# 4_cpu.net
KiCad netlist of a schematic drawn in Altium Designer
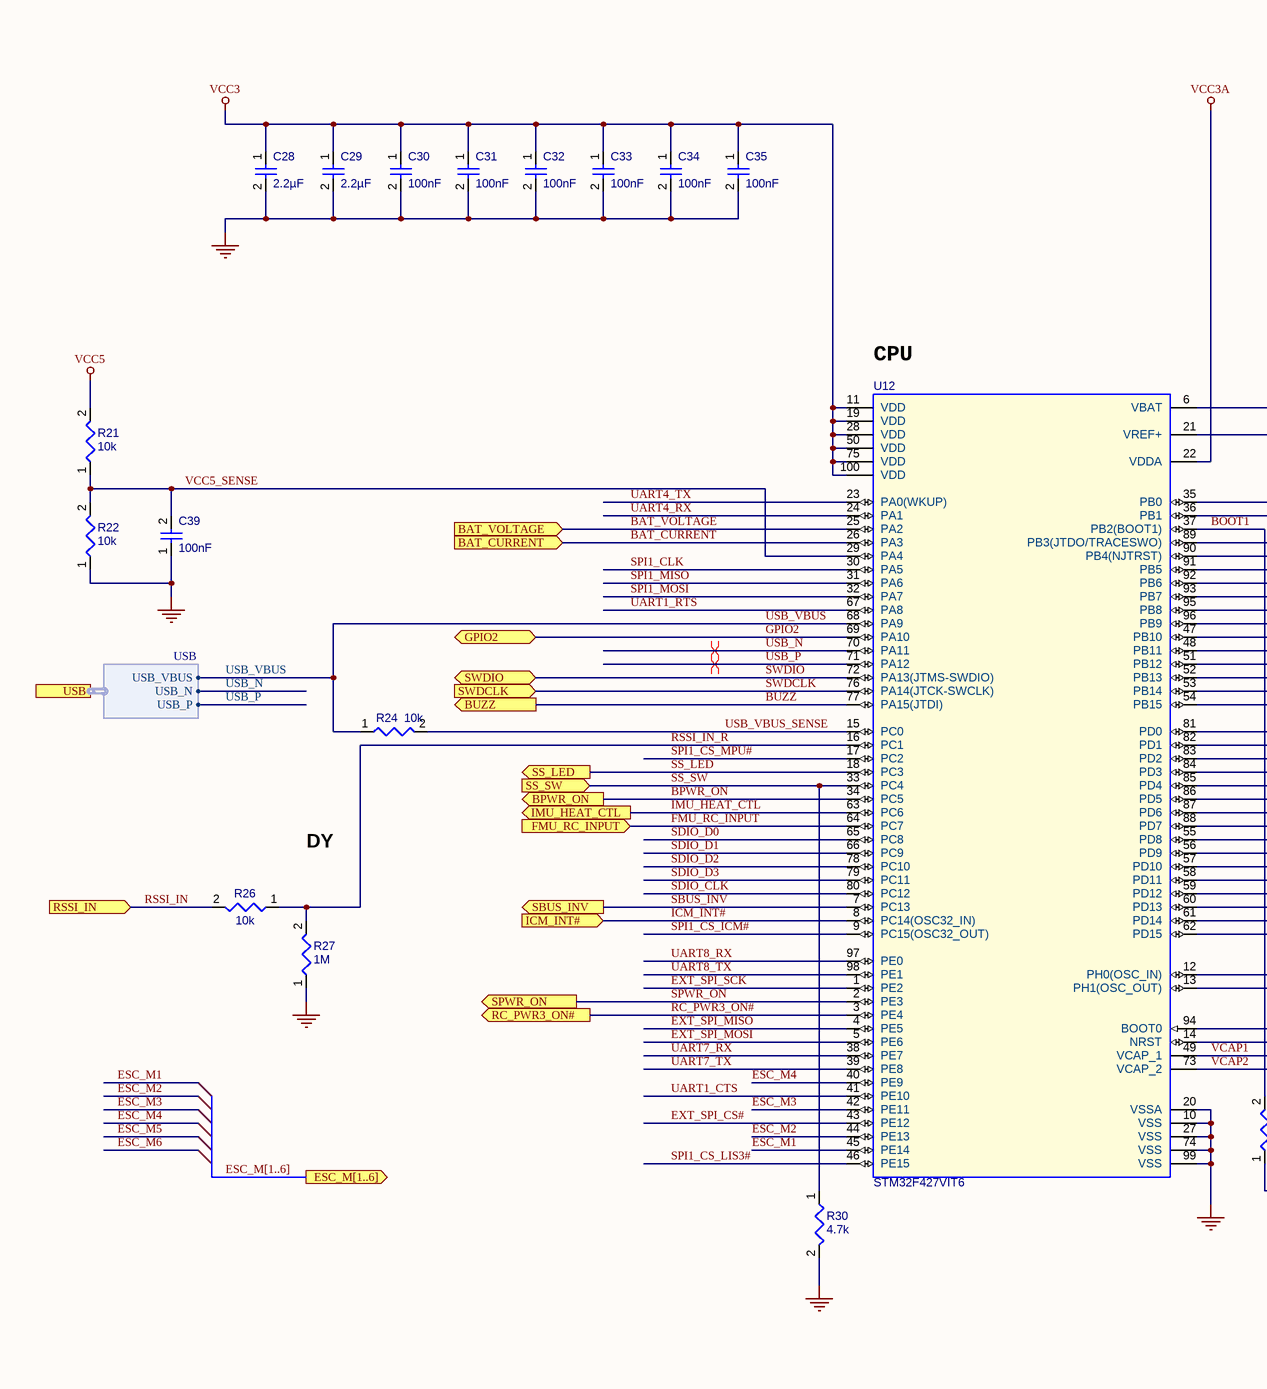
[diagram p0: 4_cpu.SchDoc, left]
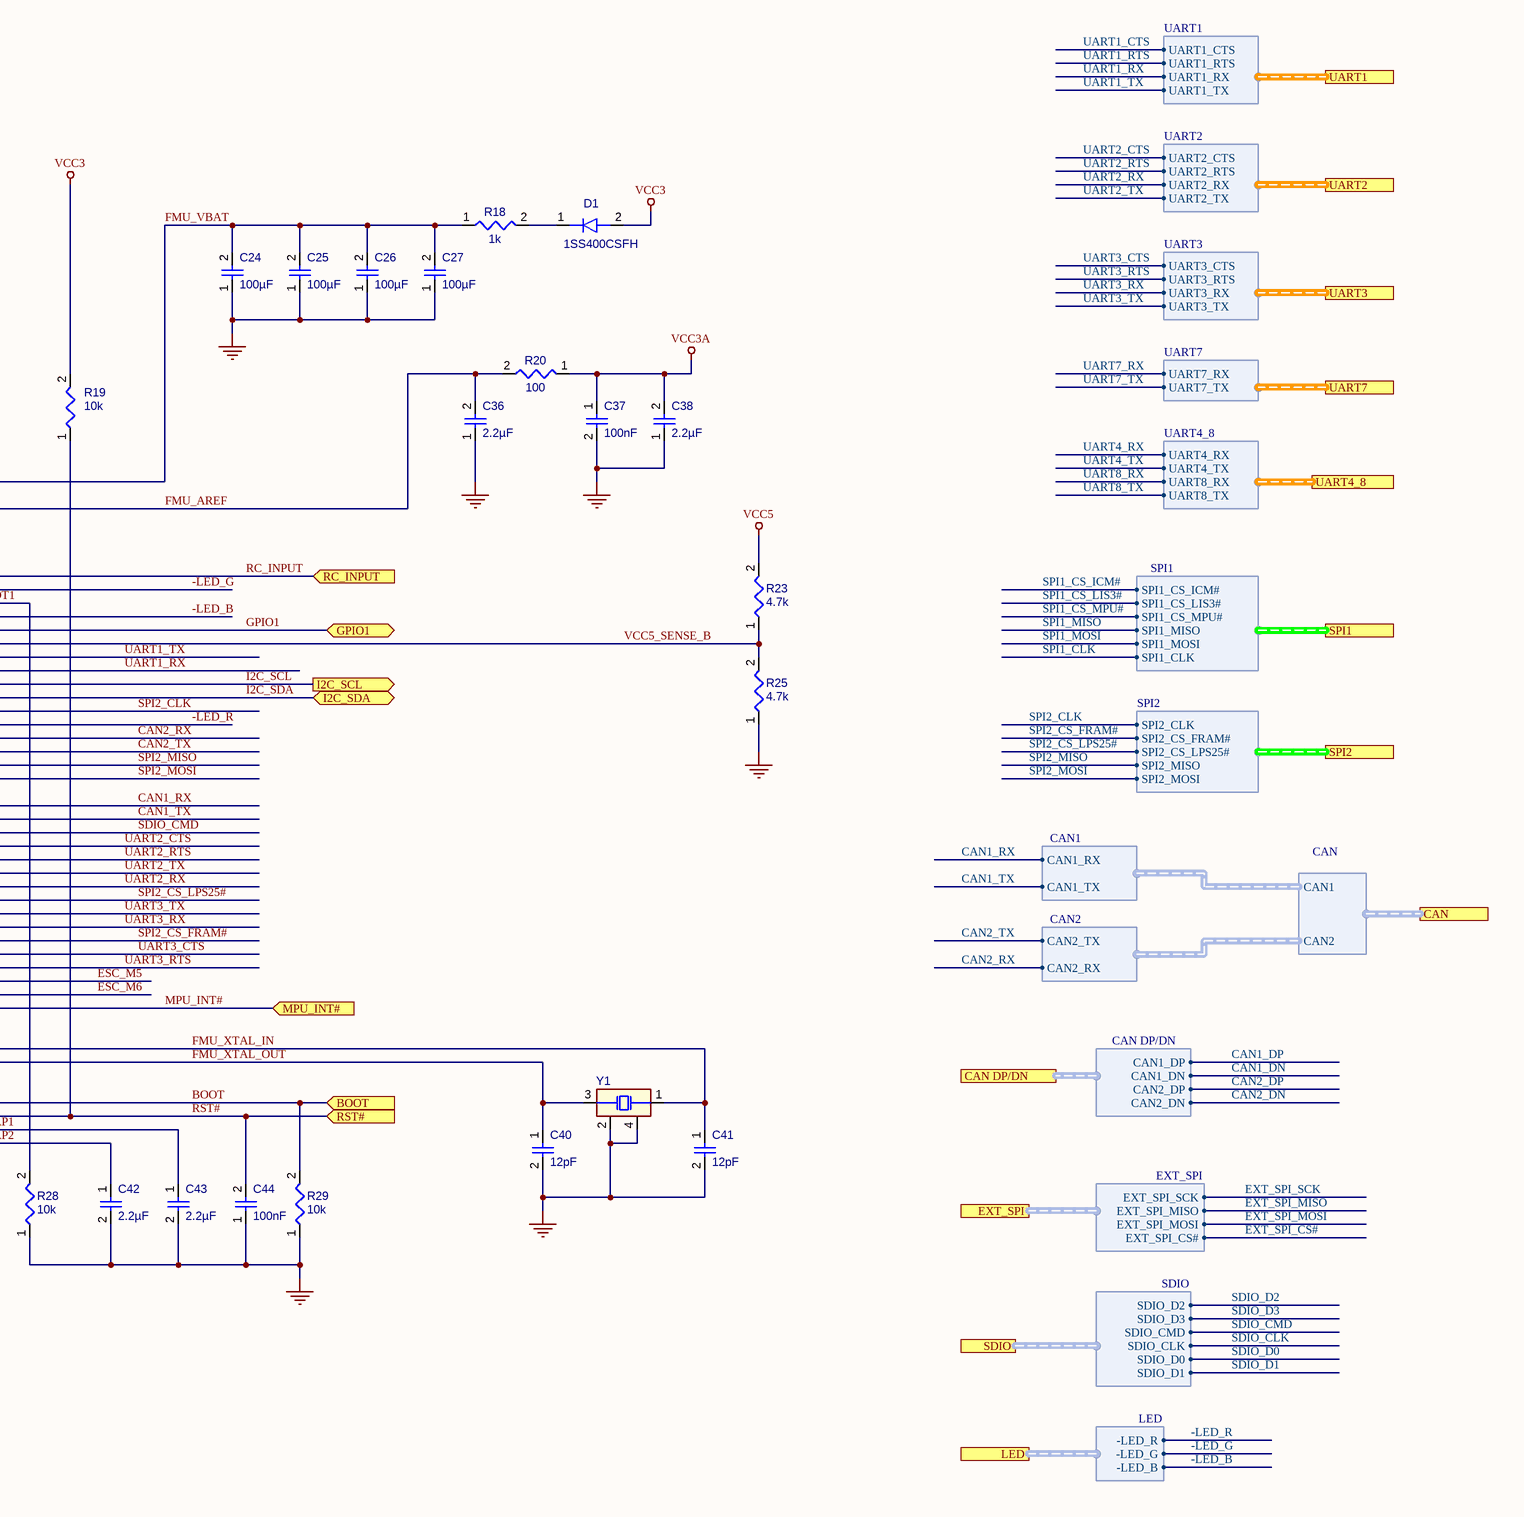
[diagram p1: 4_cpu.SchDoc, right]

(export (version "E")
  (design (tool "Eeschema 10.0.6"))
  (components
    (comp (ref "C24")
      (value "100µF")
      (footprint "CAPC0805(2012)145_L")
      (description "Chip Capacitor, 100µF +/-20%, 6.3V, 0805, Thickness 1.45 mm")
      (fields (field (name "TOLERANCE") "10%") (field (name "Comment") "Capacitor 100µF +/-20% 6.3V 0805"))
      (libsource (lib "<Company> Server") (part "CAP-NP-2"))
    )
    (comp (ref "C25")
      (value "100µF")
      (footprint "CAPC0805(2012)145_L")
      (description "Chip Capacitor, 100µF +/-20%, 6.3V, 0805, Thickness 1.45 mm")
      (fields (field (name "TOLERANCE") "10%") (field (name "Comment") "Capacitor 100µF +/-20% 6.3V 0805"))
      (libsource (lib "<Company> Server") (part "CAP-NP-2"))
    )
    (comp (ref "C26")
      (value "100µF")
      (footprint "CAPC0805(2012)145_L")
      (description "Chip Capacitor, 100µF +/-20%, 6.3V, 0805, Thickness 1.45 mm")
      (fields (field (name "TOLERANCE") "10%") (field (name "Comment") "Capacitor 100µF +/-20% 6.3V 0805"))
      (libsource (lib "<Company> Server") (part "CAP-NP-2"))
    )
    (comp (ref "C27")
      (value "100µF")
      (footprint "CAPC0805(2012)145_L")
      (description "Chip Capacitor, 100µF +/-20%, 6.3V, 0805, Thickness 1.45 mm")
      (fields (field (name "TOLERANCE") "10%") (field (name "Comment") "Capacitor 100µF +/-20% 6.3V 0805"))
      (libsource (lib "<Company> Server") (part "CAP-NP-2"))
    )
    (comp (ref "C28")
      (value "2.2µF")
      (footprint "CAPC0402(1005)60_L")
      (description "Chip Capacitor, 2,2µF +/-20%, 10V, 0402, Thickness 0.6 mm")
      (fields (field (name "TOLERANCE") "10%") (field (name "Comment") "Capacitor 2,2µF +/-20% 10V 0402"))
      (libsource (lib "<Company> Server") (part "CAP-NP-2"))
    )
    (comp (ref "C29")
      (value "2.2µF")
      (footprint "CAPC0402(1005)60_L")
      (description "Chip Capacitor, 2,2µF +/-20%, 10V, 0402, Thickness 0.6 mm")
      (fields (field (name "TOLERANCE") "10%") (field (name "Comment") "Capacitor 2,2µF +/-20% 10V 0402"))
      (libsource (lib "<Company> Server") (part "CAP-NP-2"))
    )
    (comp (ref "C30")
      (value "100nF")
      (footprint "CAPC0402(1005)60_L")
      (description "Chip Capacitor, 100nF +/-20%, 10V, 0402, Thickness 0.6 mm")
      (fields (field (name "TOLERANCE") "20%") (field (name "Comment") "Capacitor 100nF +/-20% 10V 0402"))
      (libsource (lib "<Company> Server") (part "CAP-NP-2"))
    )
    (comp (ref "C31")
      (value "100nF")
      (footprint "CAPC0402(1005)60_L")
      (description "Chip Capacitor, 100nF +/-20%, 10V, 0402, Thickness 0.6 mm")
      (fields (field (name "TOLERANCE") "20%") (field (name "Comment") "Capacitor 100nF +/-20% 10V 0402"))
      (libsource (lib "<Company> Server") (part "CAP-NP-2"))
    )
    (comp (ref "C32")
      (value "100nF")
      (footprint "CAPC0402(1005)60_L")
      (description "Chip Capacitor, 100nF +/-20%, 10V, 0402, Thickness 0.6 mm")
      (fields (field (name "TOLERANCE") "20%") (field (name "Comment") "Capacitor 100nF +/-20% 10V 0402"))
      (libsource (lib "<Company> Server") (part "CAP-NP-2"))
    )
    (comp (ref "C33")
      (value "100nF")
      (footprint "CAPC0402(1005)60_L")
      (description "Chip Capacitor, 100nF +/-20%, 10V, 0402, Thickness 0.6 mm")
      (fields (field (name "TOLERANCE") "20%") (field (name "Comment") "Capacitor 100nF +/-20% 10V 0402"))
      (libsource (lib "<Company> Server") (part "CAP-NP-2"))
    )
    (comp (ref "C34")
      (value "100nF")
      (footprint "CAPC0402(1005)60_L")
      (description "Chip Capacitor, 100nF +/-20%, 10V, 0402, Thickness 0.6 mm")
      (fields (field (name "TOLERANCE") "20%") (field (name "Comment") "Capacitor 100nF +/-20% 10V 0402"))
      (libsource (lib "<Company> Server") (part "CAP-NP-2"))
    )
    (comp (ref "C35")
      (value "100nF")
      (footprint "CAPC0402(1005)60_L")
      (description "Chip Capacitor, 100nF +/-20%, 10V, 0402, Thickness 0.6 mm")
      (fields (field (name "TOLERANCE") "20%") (field (name "Comment") "Capacitor 100nF +/-20% 10V 0402"))
      (libsource (lib "<Company> Server") (part "CAP-NP-2"))
    )
    (comp (ref "C36")
      (value "2.2µF")
      (footprint "CAPC0402(1005)60_L")
      (description "Chip Capacitor, 2,2µF +/-20%, 10V, 0402, Thickness 0.6 mm")
      (fields (field (name "TOLERANCE") "10%") (field (name "Comment") "Capacitor 2,2µF +/-20% 10V 0402"))
      (libsource (lib "<Company> Server") (part "CAP-NP-2"))
    )
    (comp (ref "C37")
      (value "100nF")
      (footprint "CAPC0402(1005)60_L")
      (description "Chip Capacitor, 100nF +/-20%, 10V, 0402, Thickness 0.6 mm")
      (fields (field (name "TOLERANCE") "20%") (field (name "Comment") "Capacitor 100nF +/-20% 10V 0402"))
      (libsource (lib "<Company> Server") (part "CAP-NP-2"))
    )
    (comp (ref "C38")
      (value "2.2µF")
      (footprint "CAPC0402(1005)60_L")
      (description "Chip Capacitor, 2,2µF +/-20%, 10V, 0402, Thickness 0.6 mm")
      (fields (field (name "TOLERANCE") "10%") (field (name "Comment") "Capacitor 2,2µF +/-20% 10V 0402"))
      (libsource (lib "<Company> Server") (part "CAP-NP-2"))
    )
    (comp (ref "C39")
      (value "100nF")
      (footprint "CAPC0402(1005)60_L")
      (description "Chip Capacitor, 100nF +/-20%, 10V, 0402, Thickness 0.6 mm")
      (fields (field (name "TOLERANCE") "20%") (field (name "Comment") "Capacitor 100nF +/-20% 10V 0402"))
      (libsource (lib "<Company> Server") (part "CAP-NP-2"))
    )
    (comp (ref "C40")
      (value "12pF")
      (footprint "CAPC0402(1005)33_L")
      (description "Chip Capacitor, 12pF +/-10%, 50V, 0402, Thickness 0.33 mm")
      (fields (field (name "TOLERANCE") "20%") (field (name "Comment") "Capacitor 12pF +/-10% 50V 0402"))
      (libsource (lib "<Company> Server") (part "CAP-NP-2"))
    )
    (comp (ref "C41")
      (value "12pF")
      (footprint "CAPC0402(1005)33_L")
      (description "Chip Capacitor, 12pF +/-10%, 50V, 0402, Thickness 0.33 mm")
      (fields (field (name "TOLERANCE") "20%") (field (name "Comment") "Capacitor 12pF +/-10% 50V 0402"))
      (libsource (lib "<Company> Server") (part "CAP-NP-2"))
    )
    (comp (ref "C42")
      (value "2.2µF")
      (footprint "CAPC0402(1005)60_L")
      (description "Chip Capacitor, 2,2µF +/-20%, 10V, 0402, Thickness 0.6 mm")
      (fields (field (name "TOLERANCE") "10%") (field (name "Comment") "Capacitor 2,2µF +/-20% 10V 0402"))
      (libsource (lib "<Company> Server") (part "CAP-NP-2"))
    )
    (comp (ref "C43")
      (value "2.2µF")
      (footprint "CAPC0402(1005)60_L")
      (description "Chip Capacitor, 2,2µF +/-20%, 10V, 0402, Thickness 0.6 mm")
      (fields (field (name "TOLERANCE") "10%") (field (name "Comment") "Capacitor 2,2µF +/-20% 10V 0402"))
      (libsource (lib "<Company> Server") (part "CAP-NP-2"))
    )
    (comp (ref "C44")
      (value "100nF")
      (footprint "CAPC0402(1005)60_L")
      (description "Chip Capacitor, 100nF +/-20%, 10V, 0402, Thickness 0.6 mm")
      (fields (field (name "TOLERANCE") "20%") (field (name "Comment") "Capacitor 100nF +/-20% 10V 0402"))
      (libsource (lib "<Company> Server") (part "CAP-NP-2"))
    )
    (comp (ref "D1")
      (value "1SS400CSFH")
      (footprint "ROHM-VMN2-2_V")
      (description "Switching Diode (High Speed Switching), 80 V, 100 mA, 2-Pin SOD-923, RoHS, Tape and Reel")
      (libsource (lib "<Company> Server") (part "D-KA-2"))
    )
    (comp (ref "R18")
      (value "1k")
      (footprint "RESC0402(1005)_L")
      (description "Chip Resistor, 1 kOhms, +/-5 %, 63 mW, -55 to 155 degC, 0402")
      (fields (field (name "TOLERANCE") "5%") (field (name "POWER") "63mW"))
      (libsource (lib "<Company> Server") (part "RES-2"))
    )
    (comp (ref "R19")
      (value "10k")
      (footprint "RESC0402(1005)_L")
      (description "Chip Resistor, 10 kOhms, +/-1 %, 63 mW, -55 to 125 degC, 0402")
      (fields (field (name "TOLERANCE") "1%") (field (name "POWER") "63mW"))
      (libsource (lib "<Company> Server") (part "RES-2"))
    )
    (comp (ref "R20")
      (value "100")
      (footprint "RESC0402(1005)_L")
      (description "Chip Resistor, 100 Ohms, +/-1 %, 63 mW, -55 to 155 degC, 0402")
      (fields (field (name "TOLERANCE") "1%") (field (name "POWER") "63mW"))
      (libsource (lib "<Company> Server") (part "RES-2"))
    )
    (comp (ref "R21")
      (value "10k")
      (footprint "RESC0402(1005)_L")
      (description "Chip Resistor, 10 kOhms, +/-1 %, 63 mW, -55 to 125 degC, 0402")
      (fields (field (name "TOLERANCE") "1%") (field (name "POWER") "63mW"))
      (libsource (lib "<Company> Server") (part "RES-2"))
    )
    (comp (ref "R22")
      (value "10k")
      (footprint "RESC0402(1005)_L")
      (description "Chip Resistor, 10 kOhms, +/-1 %, 63 mW, -55 to 125 degC, 0402")
      (fields (field (name "TOLERANCE") "1%") (field (name "POWER") "63mW"))
      (libsource (lib "<Company> Server") (part "RES-2"))
    )
    (comp (ref "R23")
      (value "4.7k")
      (footprint "RESC0402(1005)_L")
      (description "Chip Resistor, 4,7 kOhms, +/-1 %, 63 mW, -55 to 155 degC, 0402")
      (fields (field (name "TOLERANCE") "1%") (field (name "POWER") "63mW"))
      (libsource (lib "<Company> Server") (part "RES-2"))
    )
    (comp (ref "R24")
      (value "10k")
      (footprint "RESC0402(1005)_L")
      (description "Chip Resistor, 10 kOhms, +/-1 %, 63 mW, -55 to 125 degC, 0402")
      (fields (field (name "TOLERANCE") "1%") (field (name "POWER") "63mW"))
      (libsource (lib "<Company> Server") (part "RES-2"))
    )
    (comp (ref "R25")
      (value "4.7k")
      (footprint "RESC0402(1005)_L")
      (description "Chip Resistor, 4,7 kOhms, +/-1 %, 63 mW, -55 to 155 degC, 0402")
      (fields (field (name "TOLERANCE") "1%") (field (name "POWER") "63mW"))
      (libsource (lib "<Company> Server") (part "RES-2"))
    )
    (comp (ref "R26")
      (value "10k")
      (footprint "RESC0402(1005)_L")
      (description "Chip Resistor, 10 kOhms, +/-1 %, 63 mW, -55 to 125 degC, 0402")
      (fields (field (name "TOLERANCE") "1%") (field (name "POWER") "63mW"))
      (libsource (lib "<Company> Server") (part "RES-2"))
    )
    (comp (ref "R27")
      (value "1M")
      (footprint "RESC0402(1005)_L")
      (description "Chip Resistor, 1 MOhms, +/-5 %, 63 mW, -55 to 155 degC, 0402")
      (fields (field (name "TOLERANCE") "5%") (field (name "POWER") "63mW"))
      (libsource (lib "<Company> Server") (part "RES-2"))
    )
    (comp (ref "R28")
      (value "10k")
      (footprint "RESC0402(1005)_L")
      (description "Chip Resistor, 10 kOhms, +/-1 %, 63 mW, -55 to 125 degC, 0402")
      (fields (field (name "TOLERANCE") "1%") (field (name "POWER") "63mW"))
      (libsource (lib "<Company> Server") (part "RES-2"))
    )
    (comp (ref "R29")
      (value "10k")
      (footprint "RESC0402(1005)_L")
      (description "Chip Resistor, 10 kOhms, +/-1 %, 63 mW, -55 to 125 degC, 0402")
      (fields (field (name "TOLERANCE") "1%") (field (name "POWER") "63mW"))
      (libsource (lib "<Company> Server") (part "RES-2"))
    )
    (comp (ref "R30")
      (value "4.7k")
      (footprint "RESC0402(1005)_L")
      (description "Chip Resistor, 4,7 kOhms, +/-1 %, 63 mW, -55 to 155 degC, 0402")
      (fields (field (name "TOLERANCE") "1%") (field (name "POWER") "63mW"))
      (libsource (lib "<Company> Server") (part "RES-2"))
    )
    (comp (ref "U12")
      (value "STM32F427VIT6")
      (footprint "STM-LQFP100")
      (libsource (lib "<Company> Server") (part "CMP-00125-5"))
    )
    (comp (ref "Y1")
      (value "FA-12824.0000MF10Z-W3")
      (footprint "EPSON-FA-128_V")
      (description "Crystal, 24 MHz, +/- 10 ppm, -20 to 75 degC, 4-Pin SMD, RoHS, Tape and Reel")
      (libsource (lib "<Company> Server") (part "CMP-00014-7"))
    )
  )
  (nets
    (net (code "16") (name "/-LED_B") (class "Default")
      (node (ref "U12") (pin "89") (pinfunction "PB3(JTDO/TRACESWO)_89") (pintype "bidirectional"))
    )
    (net (code "17") (name "/-LED_G") (class "Default")
      (node (ref "U12") (pin "36") (pinfunction "PB1_36") (pintype "bidirectional"))
    )
    (net (code "18") (name "/-LED_R") (class "Default")
      (node (ref "U12") (pin "48") (pinfunction "PB11_48") (pintype "bidirectional"))
    )
    (net (code "19") (name "/BAT_CURRENT") (class "Default")
      (node (ref "U12") (pin "26") (pinfunction "PA3_26") (pintype "bidirectional"))
    )
    (net (code "20") (name "/BAT_VOLTAGE") (class "Default")
      (node (ref "U12") (pin "25") (pinfunction "PA2_25") (pintype "bidirectional"))
    )
    (net (code "21") (name "/BOOT") (class "Default")
      (node (ref "R29") (pin "2") (pinfunction "2_2") (pintype "passive"))
      (node (ref "U12") (pin "94") (pinfunction "BOOT0_94") (pintype "input"))
    )
    (net (code "22") (name "/BOOT1") (class "Default")
      (node (ref "R28") (pin "2") (pinfunction "2_2") (pintype "passive"))
      (node (ref "U12") (pin "37") (pinfunction "PB2(BOOT1)_37") (pintype "bidirectional"))
    )
    (net (code "23") (name "/BPWR_ON") (class "Default")
      (node (ref "U12") (pin "34") (pinfunction "PC5_34") (pintype "bidirectional"))
    )
    (net (code "24") (name "/BUZZ") (class "Default")
      (node (ref "U12") (pin "77") (pinfunction "PA15(JTDI)_77") (pintype "bidirectional"))
    )
    (net (code "27") (name "/CAN1_RX") (class "Default")
      (node (ref "U12") (pin "81") (pinfunction "PD0_81") (pintype "bidirectional"))
    )
    (net (code "28") (name "/CAN1_TX") (class "Default")
      (node (ref "U12") (pin "82") (pinfunction "PD1_82") (pintype "bidirectional"))
    )
    (net (code "31") (name "/CAN2_RX") (class "Default")
      (node (ref "U12") (pin "51") (pinfunction "PB12_51") (pintype "bidirectional"))
    )
    (net (code "32") (name "/CAN2_TX") (class "Default")
      (node (ref "U12") (pin "52") (pinfunction "PB13_52") (pintype "bidirectional"))
    )
    (net (code "34") (name "/ESC_M1") (class "Default")
      (node (ref "U12") (pin "45") (pinfunction "PE14_45") (pintype "bidirectional"))
    )
    (net (code "35") (name "/ESC_M2") (class "Default")
      (node (ref "U12") (pin "44") (pinfunction "PE13_44") (pintype "bidirectional"))
    )
    (net (code "36") (name "/ESC_M3") (class "Default")
      (node (ref "U12") (pin "42") (pinfunction "PE11_42") (pintype "bidirectional"))
    )
    (net (code "37") (name "/ESC_M4") (class "Default")
      (node (ref "U12") (pin "40") (pinfunction "PE9_40") (pintype "bidirectional"))
    )
    (net (code "38") (name "/ESC_M5") (class "Default")
      (node (ref "U12") (pin "60") (pinfunction "PD13_60") (pintype "bidirectional"))
    )
    (net (code "39") (name "/ESC_M6") (class "Default")
      (node (ref "U12") (pin "61") (pinfunction "PD14_61") (pintype "bidirectional"))
    )
    (net (code "41") (name "/EXT_SPI_CS#") (class "Default")
      (node (ref "U12") (pin "43") (pinfunction "PE12_43") (pintype "bidirectional"))
    )
    (net (code "42") (name "/EXT_SPI_MISO") (class "Default")
      (node (ref "U12") (pin "4") (pinfunction "PE5_4") (pintype "bidirectional"))
    )
    (net (code "43") (name "/EXT_SPI_MOSI") (class "Default")
      (node (ref "U12") (pin "5") (pinfunction "PE6_5") (pintype "bidirectional"))
    )
    (net (code "44") (name "/EXT_SPI_SCK") (class "Default")
      (node (ref "U12") (pin "1") (pinfunction "PE2_1") (pintype "bidirectional"))
    )
    (net (code "45") (name "/FMU_AREF") (class "Default")
      (node (ref "C36") (pin "2") (pinfunction "2_2") (pintype "passive"))
      (node (ref "R20") (pin "2") (pinfunction "2_2") (pintype "passive"))
      (node (ref "U12") (pin "21") (pinfunction "VREF+_21") (pintype "power_in"))
    )
    (net (code "46") (name "/FMU_RC_INPUT") (class "Default")
      (node (ref "U12") (pin "64") (pinfunction "PC7_64") (pintype "bidirectional"))
    )
    (net (code "47") (name "/FMU_VBAT") (class "Default")
      (node (ref "C24") (pin "2") (pinfunction "2_2") (pintype "passive"))
      (node (ref "C25") (pin "2") (pinfunction "2_2") (pintype "passive"))
      (node (ref "C26") (pin "2") (pinfunction "2_2") (pintype "passive"))
      (node (ref "C27") (pin "2") (pinfunction "2_2") (pintype "passive"))
      (node (ref "R18") (pin "1") (pinfunction "1_1") (pintype "passive"))
      (node (ref "U12") (pin "6") (pinfunction "VBAT_6") (pintype "power_in"))
    )
    (net (code "48") (name "/FMU_XTAL_IN") (class "Default")
      (node (ref "C41") (pin "1") (pinfunction "1_1") (pintype "passive"))
      (node (ref "U12") (pin "12") (pinfunction "PH0(OSC_IN)_12") (pintype "bidirectional"))
      (node (ref "Y1") (pin "1") (pinfunction "X1_1") (pintype "passive"))
    )
    (net (code "49") (name "/FMU_XTAL_OUT") (class "Default")
      (node (ref "C40") (pin "1") (pinfunction "1_1") (pintype "passive"))
      (node (ref "U12") (pin "13") (pinfunction "PH1(OSC_OUT)_13") (pintype "bidirectional"))
      (node (ref "Y1") (pin "3") (pinfunction "X2_3") (pintype "passive"))
    )
    (net (code "50") (name "/GPIO1") (class "Default")
      (node (ref "U12") (pin "90") (pinfunction "PB4(NJTRST)_90") (pintype "bidirectional"))
    )
    (net (code "51") (name "/GPIO2") (class "Default")
      (node (ref "U12") (pin "69") (pinfunction "PA10_69") (pintype "bidirectional"))
    )
    (net (code "52") (name "/I2C_SCL") (class "Default")
      (node (ref "U12") (pin "95") (pinfunction "PB8_95") (pintype "bidirectional"))
    )
    (net (code "53") (name "/I2C_SDA") (class "Default")
      (node (ref "U12") (pin "96") (pinfunction "PB9_96") (pintype "bidirectional"))
    )
    (net (code "54") (name "/ICM_INT#") (class "Default")
      (node (ref "U12") (pin "8") (pinfunction "PC14(OSC32_IN)_8") (pintype "bidirectional"))
    )
    (net (code "55") (name "/IMU_HEAT_CTL") (class "Default")
      (node (ref "U12") (pin "63") (pinfunction "PC6_63") (pintype "bidirectional"))
    )
    (net (code "56") (name "/MPU_INT#") (class "Default")
      (node (ref "U12") (pin "62") (pinfunction "PD15_62") (pintype "bidirectional"))
    )
    (net (code "57") (name "/RC_INPUT") (class "Default")
      (node (ref "U12") (pin "35") (pinfunction "PB0_35") (pintype "bidirectional"))
    )
    (net (code "58") (name "/RC_PWR3_ON#") (class "Default")
      (node (ref "U12") (pin "3") (pinfunction "PE4_3") (pintype "bidirectional"))
    )
    (net (code "59") (name "/RSSI_IN") (class "Default")
      (node (ref "R26") (pin "2") (pinfunction "2_2") (pintype "passive"))
    )
    (net (code "60") (name "/RSSI_IN_R") (class "Default")
      (node (ref "R26") (pin "1") (pinfunction "1_1") (pintype "passive"))
      (node (ref "R27") (pin "2") (pinfunction "2_2") (pintype "passive"))
      (node (ref "U12") (pin "16") (pinfunction "PC1_16") (pintype "bidirectional"))
    )
    (net (code "61") (name "/RST#") (class "Default")
      (node (ref "C44") (pin "2") (pinfunction "2_2") (pintype "passive"))
      (node (ref "R19") (pin "1") (pinfunction "1_1") (pintype "passive"))
      (node (ref "U12") (pin "14") (pinfunction "NRST_14") (pintype "bidirectional"))
    )
    (net (code "62") (name "/SBUS_INV") (class "Default")
      (node (ref "U12") (pin "7") (pinfunction "PC13_7") (pintype "bidirectional"))
    )
    (net (code "63") (name "/SDIO_CLK") (class "Default")
      (node (ref "U12") (pin "80") (pinfunction "PC12_80") (pintype "bidirectional"))
    )
    (net (code "64") (name "/SDIO_CMD") (class "Default")
      (node (ref "U12") (pin "83") (pinfunction "PD2_83") (pintype "bidirectional"))
    )
    (net (code "65") (name "/SDIO_D0") (class "Default")
      (node (ref "U12") (pin "65") (pinfunction "PC8_65") (pintype "bidirectional"))
    )
    (net (code "66") (name "/SDIO_D1") (class "Default")
      (node (ref "U12") (pin "66") (pinfunction "PC9_66") (pintype "bidirectional"))
    )
    (net (code "67") (name "/SDIO_D2") (class "Default")
      (node (ref "U12") (pin "78") (pinfunction "PC10_78") (pintype "bidirectional"))
    )
    (net (code "68") (name "/SDIO_D3") (class "Default")
      (node (ref "U12") (pin "79") (pinfunction "PC11_79") (pintype "bidirectional"))
    )
    (net (code "69") (name "/SPI1_CLK") (class "Default")
      (node (ref "U12") (pin "30") (pinfunction "PA5_30") (pintype "bidirectional"))
    )
    (net (code "70") (name "/SPI1_CS_ICM#") (class "Default")
      (node (ref "U12") (pin "9") (pinfunction "PC15(OSC32_OUT)_9") (pintype "bidirectional"))
    )
    (net (code "71") (name "/SPI1_CS_LIS3#") (class "Default")
      (node (ref "U12") (pin "46") (pinfunction "PE15_46") (pintype "bidirectional"))
    )
    (net (code "72") (name "/SPI1_CS_MPU#") (class "Default")
      (node (ref "U12") (pin "17") (pinfunction "PC2_17") (pintype "bidirectional"))
    )
    (net (code "73") (name "/SPI1_MISO") (class "Default")
      (node (ref "U12") (pin "31") (pinfunction "PA6_31") (pintype "bidirectional"))
    )
    (net (code "74") (name "/SPI1_MOSI") (class "Default")
      (node (ref "U12") (pin "32") (pinfunction "PA7_32") (pintype "bidirectional"))
    )
    (net (code "75") (name "/SPI2_CLK") (class "Default")
      (node (ref "U12") (pin "47") (pinfunction "PB10_47") (pintype "bidirectional"))
    )
    (net (code "76") (name "/SPI2_CS_FRAM#") (class "Default")
      (node (ref "U12") (pin "57") (pinfunction "PD10_57") (pintype "bidirectional"))
    )
    (net (code "77") (name "/SPI2_CS_LPS25#") (class "Default")
      (node (ref "U12") (pin "88") (pinfunction "PD7_88") (pintype "bidirectional"))
    )
    (net (code "78") (name "/SPI2_MISO") (class "Default")
      (node (ref "U12") (pin "53") (pinfunction "PB14_53") (pintype "bidirectional"))
    )
    (net (code "79") (name "/SPI2_MOSI") (class "Default")
      (node (ref "U12") (pin "54") (pinfunction "PB15_54") (pintype "bidirectional"))
    )
    (net (code "80") (name "/SPWR_ON") (class "Default")
      (node (ref "U12") (pin "2") (pinfunction "PE3_2") (pintype "bidirectional"))
    )
    (net (code "81") (name "/SS_LED") (class "Default")
      (node (ref "U12") (pin "18") (pinfunction "PC3_18") (pintype "bidirectional"))
    )
    (net (code "82") (name "/SS_SW") (class "Default")
      (node (ref "R30") (pin "1") (pinfunction "1_1") (pintype "passive"))
      (node (ref "U12") (pin "33") (pinfunction "PC4_33") (pintype "bidirectional"))
    )
    (net (code "83") (name "/SWDCLK") (class "Default")
      (node (ref "U12") (pin "76") (pinfunction "PA14(JTCK-SWCLK)_76") (pintype "bidirectional"))
    )
    (net (code "84") (name "/SWDIO") (class "Default")
      (node (ref "U12") (pin "72") (pinfunction "PA13(JTMS-SWDIO)_72") (pintype "bidirectional"))
    )
    (net (code "85") (name "/UART1_CTS") (class "Default")
      (node (ref "U12") (pin "41") (pinfunction "PE10_41") (pintype "bidirectional"))
    )
    (net (code "86") (name "/UART1_RTS") (class "Default")
      (node (ref "U12") (pin "67") (pinfunction "PA8_67") (pintype "bidirectional"))
    )
    (net (code "87") (name "/UART1_RX") (class "Default")
      (node (ref "U12") (pin "93") (pinfunction "PB7_93") (pintype "bidirectional"))
    )
    (net (code "88") (name "/UART1_TX") (class "Default")
      (node (ref "U12") (pin "92") (pinfunction "PB6_92") (pintype "bidirectional"))
    )
    (net (code "89") (name "/UART2_CTS") (class "Default")
      (node (ref "U12") (pin "84") (pinfunction "PD3_84") (pintype "bidirectional"))
    )
    (net (code "90") (name "/UART2_RTS") (class "Default")
      (node (ref "U12") (pin "85") (pinfunction "PD4_85") (pintype "bidirectional"))
    )
    (net (code "91") (name "/UART2_RX") (class "Default")
      (node (ref "U12") (pin "87") (pinfunction "PD6_87") (pintype "bidirectional"))
    )
    (net (code "92") (name "/UART2_TX") (class "Default")
      (node (ref "U12") (pin "86") (pinfunction "PD5_86") (pintype "bidirectional"))
    )
    (net (code "93") (name "/UART3_CTS") (class "Default")
      (node (ref "U12") (pin "58") (pinfunction "PD11_58") (pintype "bidirectional"))
    )
    (net (code "94") (name "/UART3_RTS") (class "Default")
      (node (ref "U12") (pin "59") (pinfunction "PD12_59") (pintype "bidirectional"))
    )
    (net (code "95") (name "/UART3_RX") (class "Default")
      (node (ref "U12") (pin "56") (pinfunction "PD9_56") (pintype "bidirectional"))
    )
    (net (code "96") (name "/UART3_TX") (class "Default")
      (node (ref "U12") (pin "55") (pinfunction "PD8_55") (pintype "bidirectional"))
    )
    (net (code "97") (name "/UART4_RX") (class "Default")
      (node (ref "U12") (pin "24") (pinfunction "PA1_24") (pintype "bidirectional"))
    )
    (net (code "98") (name "/UART4_TX") (class "Default")
      (node (ref "U12") (pin "23") (pinfunction "PA0(WKUP)_23") (pintype "bidirectional"))
    )
    (net (code "99") (name "/UART7_RX") (class "Default")
      (node (ref "U12") (pin "38") (pinfunction "PE7_38") (pintype "bidirectional"))
    )
    (net (code "100") (name "/UART7_TX") (class "Default")
      (node (ref "U12") (pin "39") (pinfunction "PE8_39") (pintype "bidirectional"))
    )
    (net (code "101") (name "/UART8_RX") (class "Default")
      (node (ref "U12") (pin "97") (pinfunction "PE0_97") (pintype "bidirectional"))
    )
    (net (code "102") (name "/UART8_TX") (class "Default")
      (node (ref "U12") (pin "98") (pinfunction "PE1_98") (pintype "bidirectional"))
    )
    (net (code "103") (name "/USB_N") (class "Default")
      (node (ref "U12") (pin "70") (pinfunction "PA11_70") (pintype "bidirectional"))
    )
    (net (code "104") (name "/USB_P") (class "Default")
      (node (ref "U12") (pin "71") (pinfunction "PA12_71") (pintype "bidirectional"))
    )
    (net (code "105") (name "/USB_VBUS") (class "Default")
      (node (ref "R24") (pin "1") (pinfunction "1_1") (pintype "passive"))
      (node (ref "U12") (pin "68") (pinfunction "PA9_68") (pintype "bidirectional"))
    )
    (net (code "106") (name "/USB_VBUS_SENSE") (class "Default")
      (node (ref "R24") (pin "2") (pinfunction "2_2") (pintype "passive"))
      (node (ref "U12") (pin "15") (pinfunction "PC0_15") (pintype "bidirectional"))
    )
    (net (code "107") (name "/VCAP1") (class "Default")
      (node (ref "C43") (pin "1") (pinfunction "1_1") (pintype "passive"))
      (node (ref "U12") (pin "49") (pinfunction "VCAP_1_49") (pintype "passive"))
    )
    (net (code "108") (name "/VCAP2") (class "Default")
      (node (ref "C42") (pin "1") (pinfunction "1_1") (pintype "passive"))
      (node (ref "U12") (pin "73") (pinfunction "VCAP_2_73") (pintype "passive"))
    )
    (net (code "109") (name "/VCC5_SENSE") (class "Default")
      (node (ref "C39") (pin "2") (pinfunction "2_2") (pintype "passive"))
      (node (ref "R21") (pin "1") (pinfunction "1_1") (pintype "passive"))
      (node (ref "R22") (pin "2") (pinfunction "2_2") (pintype "passive"))
      (node (ref "U12") (pin "29") (pinfunction "PA4_29") (pintype "bidirectional"))
    )
    (net (code "110") (name "/VCC5_SENSE_B") (class "Default")
      (node (ref "R23") (pin "1") (pinfunction "1_1") (pintype "passive"))
      (node (ref "R25") (pin "2") (pinfunction "2_2") (pintype "passive"))
      (node (ref "U12") (pin "91") (pinfunction "PB5_91") (pintype "bidirectional"))
    )
    (net (code "125") (name "GND") (class "Default")
      (node (ref "C24") (pin "1") (pinfunction "1_1") (pintype "passive"))
      (node (ref "C25") (pin "1") (pinfunction "1_1") (pintype "passive"))
      (node (ref "C26") (pin "1") (pinfunction "1_1") (pintype "passive"))
      (node (ref "C27") (pin "1") (pinfunction "1_1") (pintype "passive"))
      (node (ref "C28") (pin "2") (pinfunction "2_2") (pintype "passive"))
      (node (ref "C29") (pin "2") (pinfunction "2_2") (pintype "passive"))
      (node (ref "C30") (pin "2") (pinfunction "2_2") (pintype "passive"))
      (node (ref "C31") (pin "2") (pinfunction "2_2") (pintype "passive"))
      (node (ref "C32") (pin "2") (pinfunction "2_2") (pintype "passive"))
      (node (ref "C33") (pin "2") (pinfunction "2_2") (pintype "passive"))
      (node (ref "C34") (pin "2") (pinfunction "2_2") (pintype "passive"))
      (node (ref "C35") (pin "2") (pinfunction "2_2") (pintype "passive"))
      (node (ref "C36") (pin "1") (pinfunction "1_1") (pintype "passive"))
      (node (ref "C37") (pin "2") (pinfunction "2_2") (pintype "passive"))
      (node (ref "C38") (pin "1") (pinfunction "1_1") (pintype "passive"))
      (node (ref "C39") (pin "1") (pinfunction "1_1") (pintype "passive"))
      (node (ref "C40") (pin "2") (pinfunction "2_2") (pintype "passive"))
      (node (ref "C41") (pin "2") (pinfunction "2_2") (pintype "passive"))
      (node (ref "C42") (pin "2") (pinfunction "2_2") (pintype "passive"))
      (node (ref "C43") (pin "2") (pinfunction "2_2") (pintype "passive"))
      (node (ref "C44") (pin "1") (pinfunction "1_1") (pintype "passive"))
      (node (ref "R22") (pin "1") (pinfunction "1_1") (pintype "passive"))
      (node (ref "R25") (pin "1") (pinfunction "1_1") (pintype "passive"))
      (node (ref "R27") (pin "1") (pinfunction "1_1") (pintype "passive"))
      (node (ref "R28") (pin "1") (pinfunction "1_1") (pintype "passive"))
      (node (ref "R29") (pin "1") (pinfunction "1_1") (pintype "passive"))
      (node (ref "R30") (pin "2") (pinfunction "2_2") (pintype "passive"))
      (node (ref "U12") (pin "10") (pinfunction "VSS_10") (pintype "power_in"))
      (node (ref "U12") (pin "20") (pinfunction "VSSA_20") (pintype "power_in"))
      (node (ref "U12") (pin "27") (pinfunction "VSS_27") (pintype "power_in"))
      (node (ref "U12") (pin "74") (pinfunction "VSS_74") (pintype "power_in"))
      (node (ref "U12") (pin "99") (pinfunction "VSS_99") (pintype "power_in"))
      (node (ref "Y1") (pin "2") (pinfunction "NC_2") (pintype "power_in"))
      (node (ref "Y1") (pin "4") (pinfunction "NC_4") (pintype "power_in"))
    )
    (net (code "126") (name "Net-(D1-K)") (class "Default")
      (node (ref "D1") (pin "1") (pinfunction "K_1") (pintype "passive"))
      (node (ref "R18") (pin "2") (pinfunction "2_2") (pintype "passive"))
    )
    (net (code "127") (name "VCC3") (class "Default")
      (node (ref "C28") (pin "1") (pinfunction "1_1") (pintype "passive"))
      (node (ref "C29") (pin "1") (pinfunction "1_1") (pintype "passive"))
      (node (ref "C30") (pin "1") (pinfunction "1_1") (pintype "passive"))
      (node (ref "C31") (pin "1") (pinfunction "1_1") (pintype "passive"))
      (node (ref "C32") (pin "1") (pinfunction "1_1") (pintype "passive"))
      (node (ref "C33") (pin "1") (pinfunction "1_1") (pintype "passive"))
      (node (ref "C34") (pin "1") (pinfunction "1_1") (pintype "passive"))
      (node (ref "C35") (pin "1") (pinfunction "1_1") (pintype "passive"))
      (node (ref "D1") (pin "2") (pinfunction "A_2") (pintype "passive"))
      (node (ref "R19") (pin "2") (pinfunction "2_2") (pintype "passive"))
      (node (ref "U12") (pin "100") (pinfunction "VDD_100") (pintype "power_in"))
      (node (ref "U12") (pin "11") (pinfunction "VDD_11") (pintype "power_in"))
      (node (ref "U12") (pin "19") (pinfunction "VDD_19") (pintype "power_in"))
      (node (ref "U12") (pin "28") (pinfunction "VDD_28") (pintype "power_in"))
      (node (ref "U12") (pin "50") (pinfunction "VDD_50") (pintype "power_in"))
      (node (ref "U12") (pin "75") (pinfunction "VDD_75") (pintype "power_in"))
    )
    (net (code "128") (name "VCC3A") (class "Default")
      (node (ref "C37") (pin "1") (pinfunction "1_1") (pintype "passive"))
      (node (ref "C38") (pin "2") (pinfunction "2_2") (pintype "passive"))
      (node (ref "R20") (pin "1") (pinfunction "1_1") (pintype "passive"))
      (node (ref "U12") (pin "22") (pinfunction "VDDA_22") (pintype "power_in"))
    )
    (net (code "129") (name "VCC5") (class "Default")
      (node (ref "R21") (pin "2") (pinfunction "2_2") (pintype "passive"))
      (node (ref "R23") (pin "2") (pinfunction "2_2") (pintype "passive"))
    )
  )
)
